# usbtinyisp_v2_0_SS.net
KiCad netlist of a schematic drawn in EAGLE
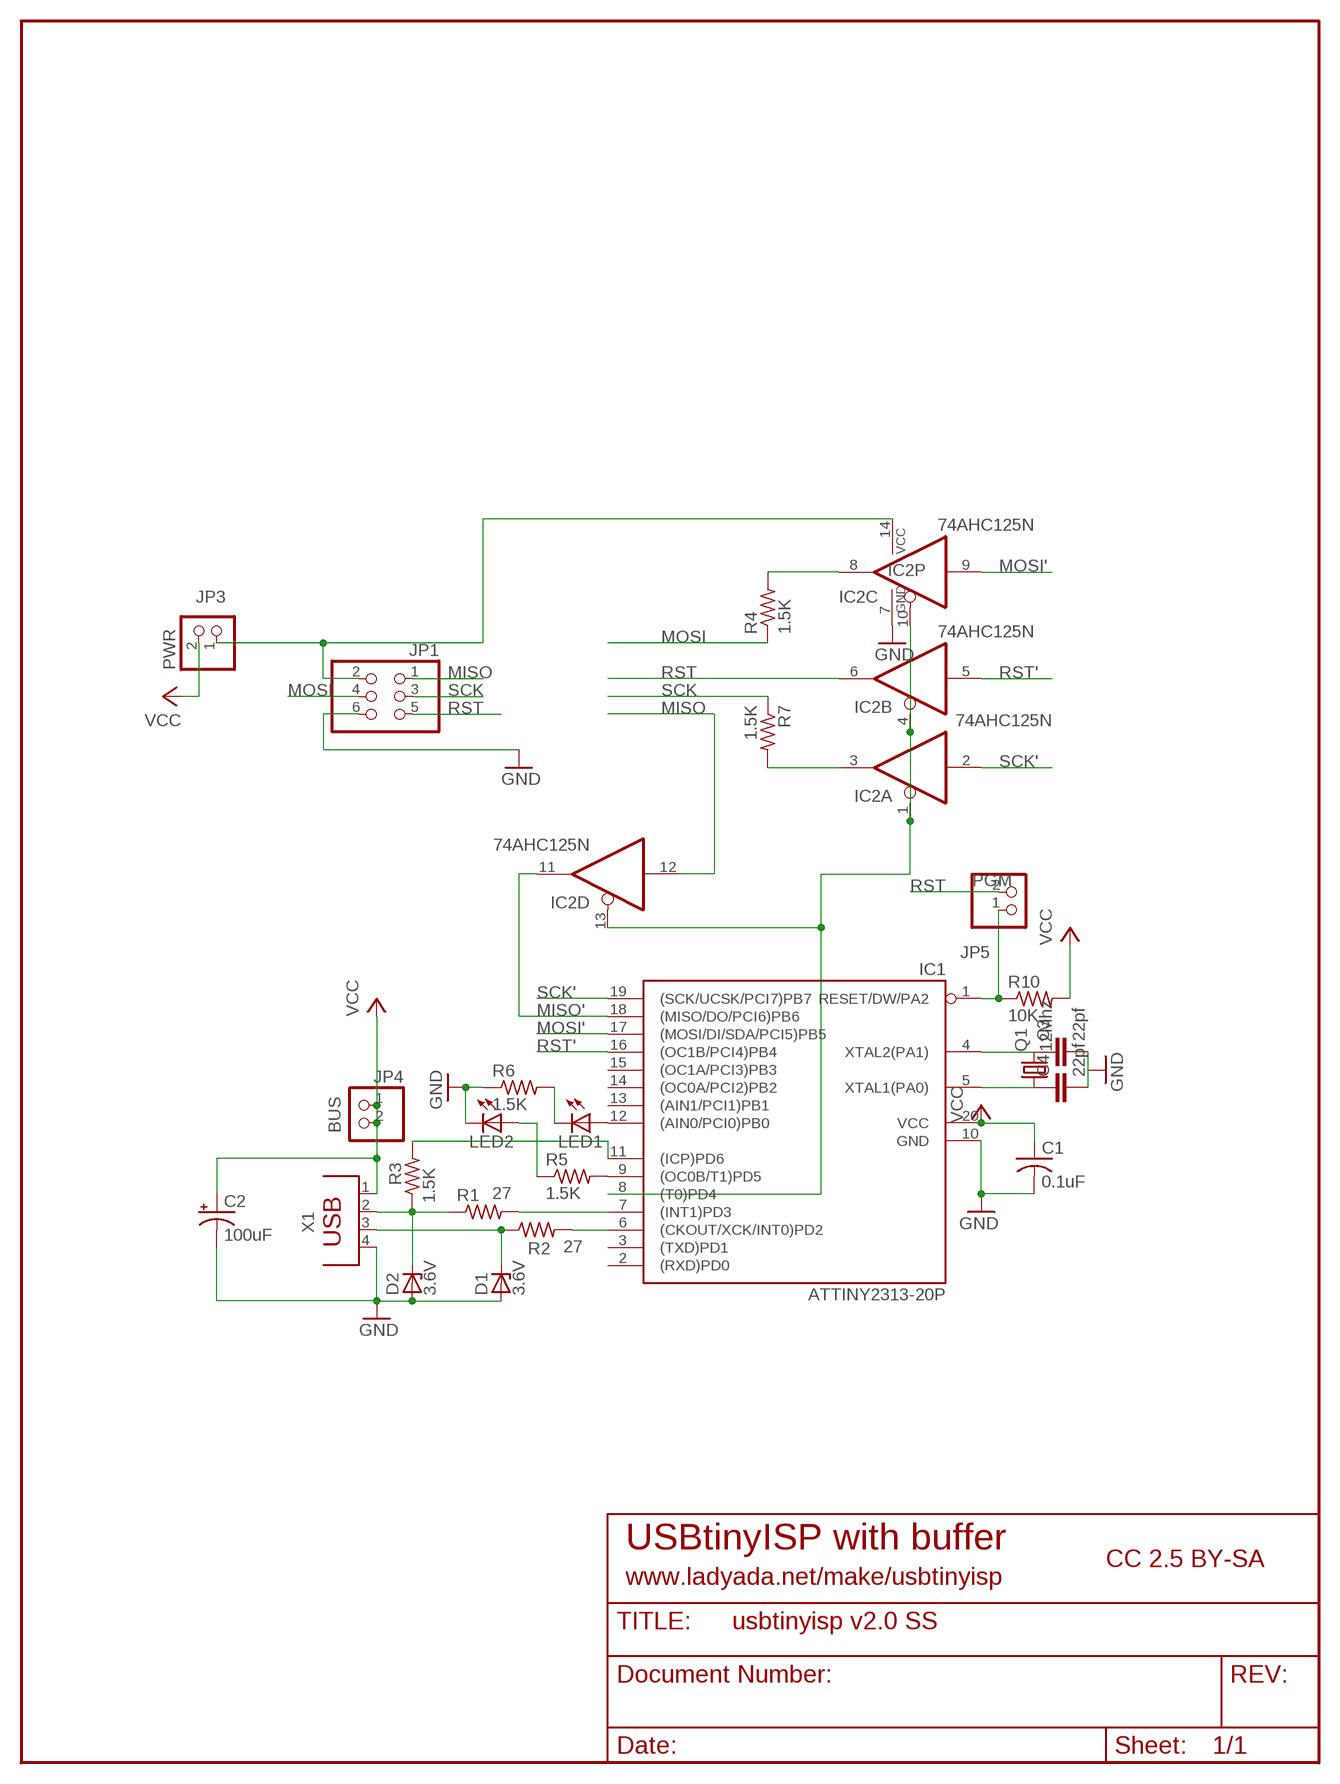
[diagram p0: schematic, sheet 1]

(export (version "E")
  (design (tool "Eeschema 10.0.6"))
  (components
    (comp (ref "C1")
      (value "0.1uF")
      (footprint "eagle-import:C025-025X050")
      (libsource (lib "eagle-import") (part "C-US025-025X050"))
    )
    (comp (ref "C2")
      (value "100uF")
      (footprint "eagle-import:E2,5-5")
      (libsource (lib "eagle-import") (part "CPOL-USE2.5-5"))
    )
    (comp (ref "C3")
      (value "22pf")
      (footprint "eagle-import:C025-025X050")
      (libsource (lib "eagle-import") (part "C-EU025-025X050"))
    )
    (comp (ref "C4")
      (value "22pf")
      (footprint "eagle-import:C025-025X050")
      (libsource (lib "eagle-import") (part "C-EU025-025X050"))
    )
    (comp (ref "D1")
      (value "3.6V")
      (footprint "eagle-import:DO35Z10")
      (libsource (lib "eagle-import") (part "ZENER-DIODEDO35Z10"))
    )
    (comp (ref "D2")
      (value "3.6V")
      (footprint "eagle-import:DO35Z10")
      (libsource (lib "eagle-import") (part "ZENER-DIODEDO35Z10"))
    )
    (comp (ref "IC1")
      (value "ATTINY2313-20P")
      (footprint "eagle-import:DIL20")
      (libsource (lib "eagle-import") (part "ATTINY2313P-20"))
    )
    (comp (ref "IC2")
      (value "74AHC125N")
      (footprint "eagle-import:DIL14")
      (libsource (lib "eagle-import") (part "74125NHC"))
    )
    (comp (ref "JP1")
      (value "PINHD-2X3")
      (footprint "eagle-import:2X03")
      (libsource (lib "eagle-import") (part "PINHD-2X3"))
    )
    (comp (ref "JP3")
      (value "PWR")
      (footprint "eagle-import:1X02")
      (libsource (lib "eagle-import") (part "PINHD-1X2"))
    )
    (comp (ref "JP4")
      (value "BUS")
      (footprint "eagle-import:1X02")
      (libsource (lib "eagle-import") (part "PINHD-1X2"))
    )
    (comp (ref "JP5")
      (value "PGM")
      (footprint "eagle-import:1X02")
      (libsource (lib "eagle-import") (part "PINHD-1X2"))
    )
    (comp (ref "LED1")
      (value "LED3MM")
      (footprint "eagle-import:LED3MM")
      (libsource (lib "eagle-import") (part "LED3MM"))
    )
    (comp (ref "LED2")
      (value "LED3MM")
      (footprint "eagle-import:LED3MM")
      (libsource (lib "eagle-import") (part "LED3MM"))
    )
    (comp (ref "Q1")
      (value "12Mhz")
      (footprint "eagle-import:HC49_S")
      (libsource (lib "eagle-import") (part "CRYSTALHC49S"))
    )
    (comp (ref "R1")
      (value "27")
      (footprint "eagle-import:0207_10")
      (libsource (lib "eagle-import") (part "R-US_0207/10"))
    )
    (comp (ref "R2")
      (value "27")
      (footprint "eagle-import:0207_7")
      (libsource (lib "eagle-import") (part "R-US_0207/7"))
    )
    (comp (ref "R3")
      (value "1.5K")
      (footprint "eagle-import:0207_5V")
      (libsource (lib "eagle-import") (part "R-US_0207/5V"))
    )
    (comp (ref "R4")
      (value "1.5K")
      (footprint "eagle-import:0207_10")
      (libsource (lib "eagle-import") (part "R-US_0207/10"))
    )
    (comp (ref "R5")
      (value "1.5K")
      (footprint "eagle-import:0207_5V")
      (libsource (lib "eagle-import") (part "R-US_0207/5V"))
    )
    (comp (ref "R6")
      (value "1.5K")
      (footprint "eagle-import:0207_5V")
      (libsource (lib "eagle-import") (part "R-US_0207/5V"))
    )
    (comp (ref "R7")
      (value "1.5K")
      (footprint "eagle-import:0204_5")
      (libsource (lib "eagle-import") (part "R-US_0204/5"))
    )
    (comp (ref "R10")
      (value "10K")
      (footprint "eagle-import:0207_10")
      (libsource (lib "eagle-import") (part "R-US_0207/10"))
    )
    (comp (ref "X1")
      (value "PN61729")
      (footprint "eagle-import:PN61729")
      (libsource (lib "eagle-import") (part "PN61729"))
    )
  )
  (nets
    (net (code "1") (name "/MISO") (class "Default")
      (node (ref "IC2") (pin "12") (pinfunction "I_12") (pintype "input"))
      (node (ref "JP1") (pin "1") (pinfunction "1_1") (pintype "passive"))
    )
    (net (code "2") (name "/MISO'") (class "Default")
      (node (ref "IC1") (pin "18") (pinfunction "(MISO/DO/PCI6)PB6_18") (pintype "bidirectional"))
      (node (ref "IC2") (pin "11") (pinfunction "O_11") (pintype "tri_state"))
    )
    (net (code "3") (name "/MOSI") (class "Default")
      (node (ref "JP1") (pin "4") (pinfunction "4_4") (pintype "passive"))
      (node (ref "R4") (pin "1") (pinfunction "1_1") (pintype "passive"))
    )
    (net (code "4") (name "/MOSI'") (class "Default")
      (node (ref "IC1") (pin "17") (pinfunction "(MOSI/DI/SDA/PCI5)PB5_17") (pintype "bidirectional"))
      (node (ref "IC2") (pin "9") (pinfunction "I_9") (pintype "input"))
    )
    (net (code "5") (name "/RST") (class "Default")
      (node (ref "IC2") (pin "6") (pinfunction "O_6") (pintype "tri_state"))
      (node (ref "JP1") (pin "5") (pinfunction "5_5") (pintype "passive"))
      (node (ref "JP5") (pin "2") (pinfunction "2_2") (pintype "passive"))
    )
    (net (code "6") (name "/RST'") (class "Default")
      (node (ref "IC1") (pin "16") (pinfunction "(OC1B/PCI4)PB4_16") (pintype "bidirectional"))
      (node (ref "IC2") (pin "5") (pinfunction "I_5") (pintype "input"))
    )
    (net (code "7") (name "/SCK") (class "Default")
      (node (ref "JP1") (pin "3") (pinfunction "3_3") (pintype "passive"))
      (node (ref "R7") (pin "1") (pinfunction "1_1") (pintype "passive"))
    )
    (net (code "8") (name "/SCK'") (class "Default")
      (node (ref "IC1") (pin "19") (pinfunction "(SCK/UCSK/PCI7)PB7_19") (pintype "bidirectional"))
      (node (ref "IC2") (pin "2") (pinfunction "I_2") (pintype "input"))
    )
    (net (code "9") (name "GND") (class "Default")
      (node (ref "C1") (pin "2") (pinfunction "2_2") (pintype "passive"))
      (node (ref "C2") (pin "-") (pinfunction "-_-") (pintype "passive"))
      (node (ref "C3") (pin "2") (pinfunction "2_2") (pintype "passive"))
      (node (ref "C4") (pin "2") (pinfunction "2_2") (pintype "passive"))
      (node (ref "D1") (pin "A") (pinfunction "A_A") (pintype "passive"))
      (node (ref "D2") (pin "A") (pinfunction "A_A") (pintype "passive"))
      (node (ref "IC1") (pin "10") (pinfunction "GND_10") (pintype "power_in"))
      (node (ref "IC2") (pin "7") (pinfunction "GND_7") (pintype "power_in"))
      (node (ref "JP1") (pin "6") (pinfunction "6_6") (pintype "passive"))
      (node (ref "LED2") (pin "K") (pinfunction "C_K") (pintype "passive"))
      (node (ref "R6") (pin "1") (pinfunction "1_1") (pintype "passive"))
      (node (ref "X1") (pin "4") (pinfunction "4_4") (pintype "bidirectional"))
    )
    (net (code "10") (name "Net-(D1-PadC)") (class "Default")
      (node (ref "D1") (pin "C") (pinfunction "C_C") (pintype "passive"))
      (node (ref "R2") (pin "1") (pinfunction "1_1") (pintype "passive"))
      (node (ref "X1") (pin "3") (pinfunction "3_3") (pintype "bidirectional"))
    )
    (net (code "11") (name "Net-(D2-PadC)") (class "Default")
      (node (ref "D2") (pin "C") (pinfunction "C_C") (pintype "passive"))
      (node (ref "R1") (pin "1") (pinfunction "1_1") (pintype "passive"))
      (node (ref "R3") (pin "1") (pinfunction "1_1") (pintype "passive"))
      (node (ref "X1") (pin "2") (pinfunction "2_2") (pintype "bidirectional"))
    )
    (net (code "12") (name "Net-(IC1-(AIN0{slash}PCI0)PB0)") (class "Default")
      (node (ref "IC1") (pin "12") (pinfunction "(AIN0/PCI0)PB0_12") (pintype "bidirectional"))
      (node (ref "LED1") (pin "A") (pinfunction "A_A") (pintype "passive"))
    )
    (net (code "13") (name "Net-(IC1-(CKOUT{slash}XCK{slash}INT0)PD2)") (class "Default")
      (node (ref "IC1") (pin "6") (pinfunction "(CKOUT/XCK/INT0)PD2_6") (pintype "bidirectional"))
      (node (ref "R2") (pin "2") (pinfunction "2_2") (pintype "passive"))
    )
    (net (code "14") (name "Net-(IC1-(ICP)PD6)") (class "Default")
      (node (ref "IC1") (pin "11") (pinfunction "(ICP)PD6_11") (pintype "bidirectional"))
      (node (ref "R3") (pin "2") (pinfunction "2_2") (pintype "passive"))
    )
    (net (code "15") (name "Net-(IC1-(INT1)PD3)") (class "Default")
      (node (ref "IC1") (pin "7") (pinfunction "(INT1)PD3_7") (pintype "bidirectional"))
      (node (ref "R1") (pin "2") (pinfunction "2_2") (pintype "passive"))
    )
    (net (code "16") (name "Net-(IC1-(OC0B{slash}T1)PD5)") (class "Default")
      (node (ref "IC1") (pin "9") (pinfunction "(OC0B/T1)PD5_9") (pintype "bidirectional"))
      (node (ref "R5") (pin "2") (pinfunction "2_2") (pintype "passive"))
    )
    (net (code "17") (name "Net-(IC1-(T0)PD4)") (class "Default")
      (node (ref "IC1") (pin "8") (pinfunction "(T0)PD4_8") (pintype "bidirectional"))
      (node (ref "IC2") (pin "1") (pinfunction "OE_1") (pintype "input"))
      (node (ref "IC2") (pin "10") (pinfunction "OE_10") (pintype "input"))
      (node (ref "IC2") (pin "13") (pinfunction "OE_13") (pintype "input"))
      (node (ref "IC2") (pin "4") (pinfunction "OE_4") (pintype "input"))
    )
    (net (code "18") (name "Net-(IC1-RESET{slash}DW{slash}PA2)") (class "Default")
      (node (ref "IC1") (pin "1") (pinfunction "RESET/DW/PA2_1") (pintype "bidirectional"))
      (node (ref "JP5") (pin "1") (pinfunction "1_1") (pintype "passive"))
      (node (ref "R10") (pin "1") (pinfunction "1_1") (pintype "passive"))
    )
    (net (code "19") (name "Net-(IC1-XTAL1(PA0))") (class "Default")
      (node (ref "C4") (pin "1") (pinfunction "1_1") (pintype "passive"))
      (node (ref "IC1") (pin "5") (pinfunction "XTAL1(PA0)_5") (pintype "bidirectional"))
      (node (ref "Q1") (pin "1") (pinfunction "1_1") (pintype "passive"))
    )
    (net (code "20") (name "Net-(IC1-XTAL2(PA1))") (class "Default")
      (node (ref "C3") (pin "1") (pinfunction "1_1") (pintype "passive"))
      (node (ref "IC1") (pin "4") (pinfunction "XTAL2(PA1)_4") (pintype "bidirectional"))
      (node (ref "Q1") (pin "2") (pinfunction "2_2") (pintype "passive"))
    )
    (net (code "21") (name "Net-(IC2A-O)") (class "Default")
      (node (ref "IC2") (pin "3") (pinfunction "O_3") (pintype "tri_state"))
      (node (ref "R7") (pin "2") (pinfunction "2_2") (pintype "passive"))
    )
    (net (code "22") (name "Net-(IC2C-O)") (class "Default")
      (node (ref "IC2") (pin "8") (pinfunction "O_8") (pintype "tri_state"))
      (node (ref "R4") (pin "2") (pinfunction "2_2") (pintype "passive"))
    )
    (net (code "23") (name "Net-(IC2E-VCC)") (class "Default")
      (node (ref "IC2") (pin "14") (pinfunction "VCC_14") (pintype "power_in"))
      (node (ref "JP1") (pin "2") (pinfunction "2_2") (pintype "passive"))
      (node (ref "JP3") (pin "1") (pinfunction "1_1") (pintype "passive"))
    )
    (net (code "24") (name "Net-(LED1-C)") (class "Default")
      (node (ref "LED1") (pin "K") (pinfunction "C_K") (pintype "passive"))
      (node (ref "R6") (pin "2") (pinfunction "2_2") (pintype "passive"))
    )
    (net (code "25") (name "Net-(LED2-PadA)") (class "Default")
      (node (ref "LED2") (pin "A") (pinfunction "A_A") (pintype "passive"))
      (node (ref "R5") (pin "1") (pinfunction "1_1") (pintype "passive"))
    )
    (net (code "26") (name "VCC") (class "Default")
      (node (ref "C1") (pin "1") (pinfunction "1_1") (pintype "passive"))
      (node (ref "C2") (pin "+") (pinfunction "+_+") (pintype "passive"))
      (node (ref "IC1") (pin "20") (pinfunction "VCC_20") (pintype "power_in"))
      (node (ref "JP3") (pin "2") (pinfunction "2_2") (pintype "passive"))
      (node (ref "JP4") (pin "1") (pinfunction "1_1") (pintype "passive"))
      (node (ref "JP4") (pin "2") (pinfunction "2_2") (pintype "passive"))
      (node (ref "R10") (pin "2") (pinfunction "2_2") (pintype "passive"))
      (node (ref "X1") (pin "1") (pinfunction "1_1") (pintype "bidirectional"))
    )
    (net (code "27") (name "unconnected-(IC1-(AIN1{slash}PCI1)PB1-Pad13)") (class "Default")
      (node (ref "IC1") (pin "13") (pinfunction "(AIN1/PCI1)PB1_13") (pintype "bidirectional"))
    )
    (net (code "28") (name "unconnected-(IC1-(OC0A{slash}PCI2)PB2-Pad14)") (class "Default")
      (node (ref "IC1") (pin "14") (pinfunction "(OC0A/PCI2)PB2_14") (pintype "bidirectional"))
    )
    (net (code "29") (name "unconnected-(IC1-(OC1A{slash}PCI3)PB3-Pad15)") (class "Default")
      (node (ref "IC1") (pin "15") (pinfunction "(OC1A/PCI3)PB3_15") (pintype "bidirectional"))
    )
    (net (code "30") (name "unconnected-(IC1-(RXD)PD0-Pad2)") (class "Default")
      (node (ref "IC1") (pin "2") (pinfunction "(RXD)PD0_2") (pintype "bidirectional"))
    )
    (net (code "31") (name "unconnected-(IC1-(TXD)PD1-Pad3)") (class "Default")
      (node (ref "IC1") (pin "3") (pinfunction "(TXD)PD1_3") (pintype "bidirectional"))
    )
  )
)
